# RoomIndicator_Outside.net
KiCad netlist of a schematic drawn in EAGLE
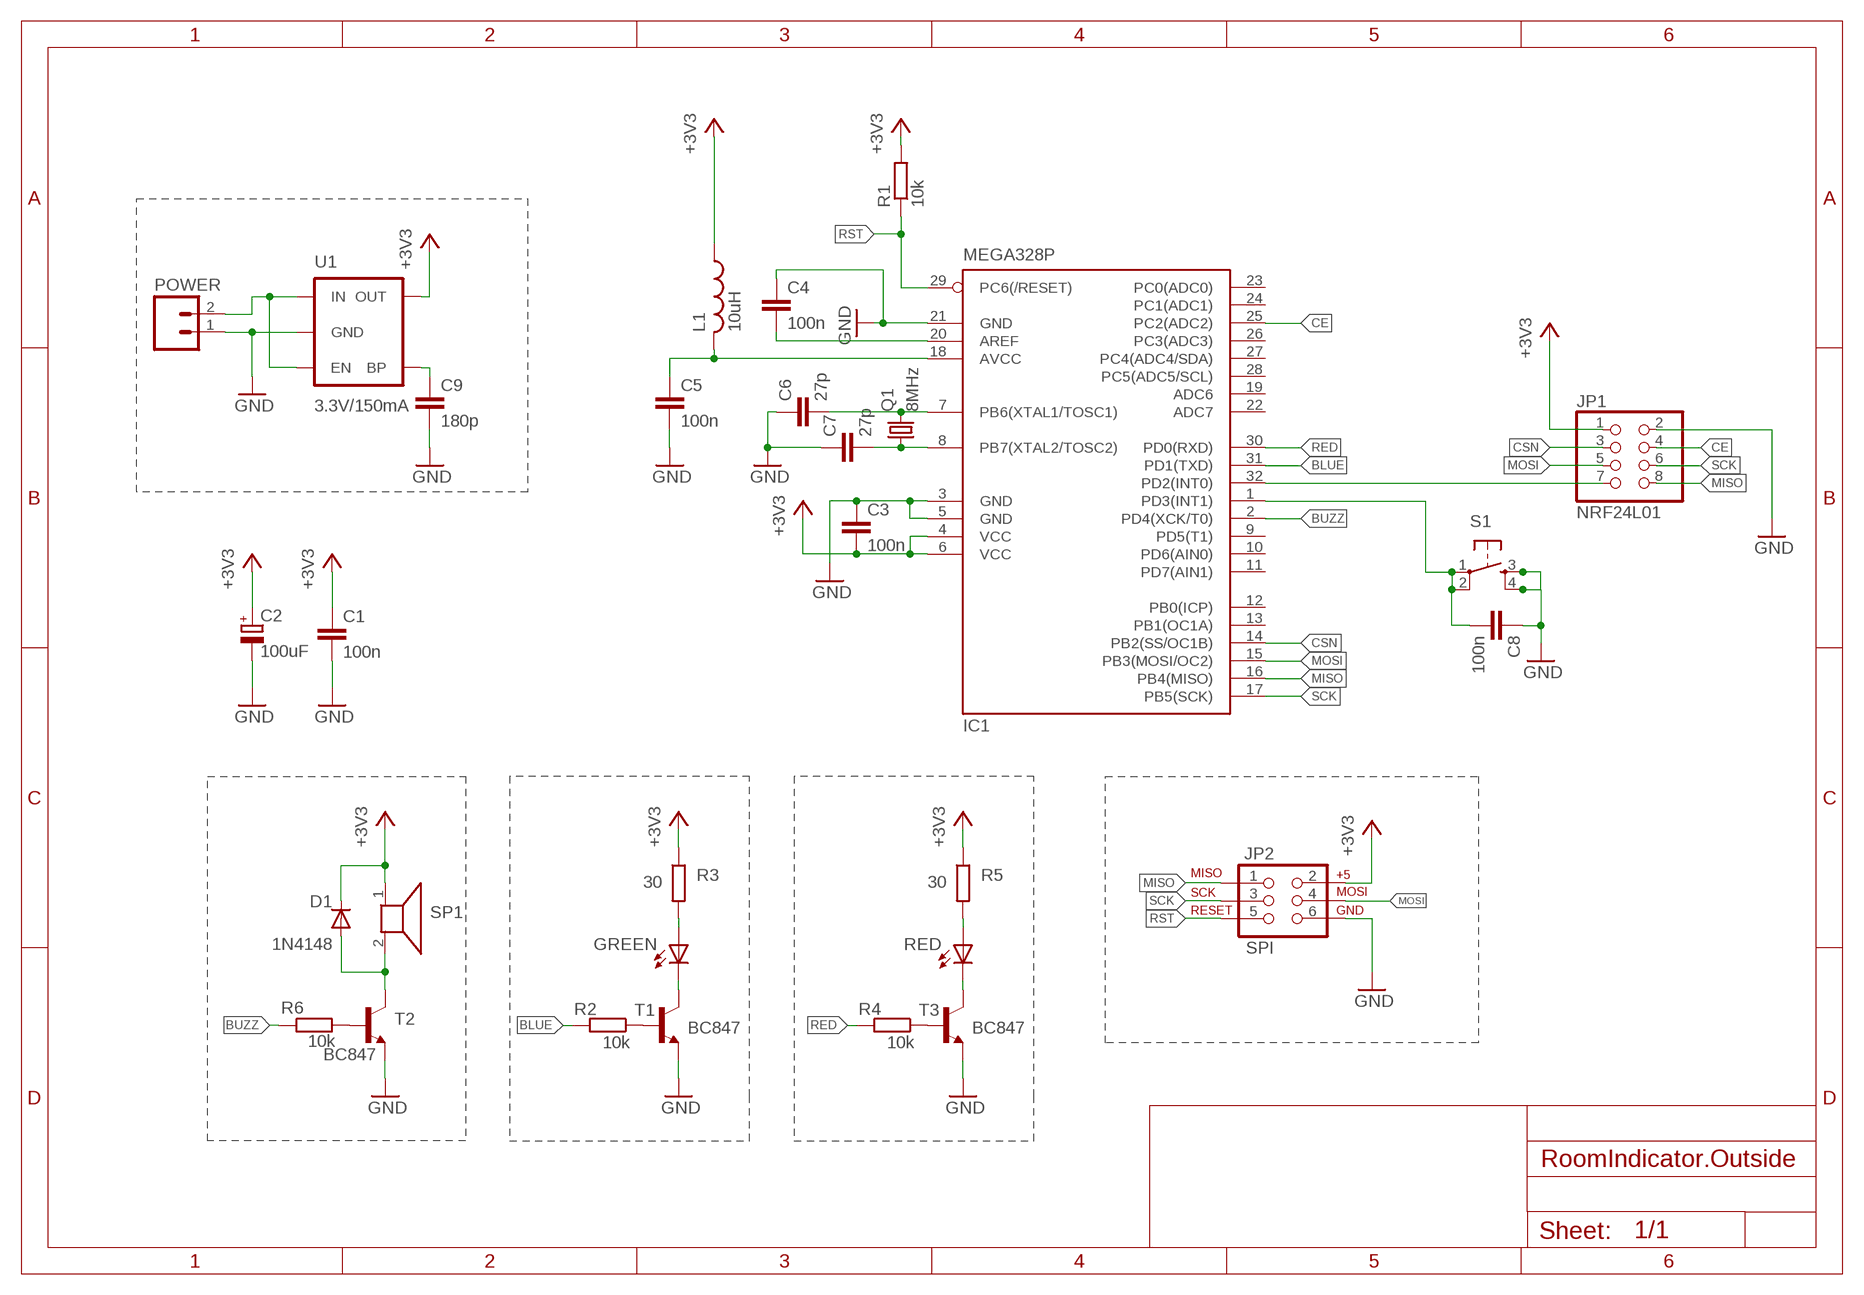
[diagram p0: schematic, sheet 1]

(export (version "E")
  (design (tool "Eeschema 10.0.6"))
  (components
    (comp (ref "C1")
      (value "100n")
      (footprint "eagle-import:C025-025X050")
      (libsource (lib "eagle-import") (part "C-EU025-025X050"))
    )
    (comp (ref "C2")
      (value "100uF")
      (footprint "eagle-import:E2,5-5")
      (libsource (lib "eagle-import") (part "CPOL-EUE2.5-5"))
    )
    (comp (ref "C3")
      (value "100n")
      (footprint "eagle-import:C0805K")
      (libsource (lib "eagle-import") (part "C-EUC0805K"))
    )
    (comp (ref "C4")
      (value "100n")
      (footprint "eagle-import:C0805K")
      (libsource (lib "eagle-import") (part "C-EUC0805K"))
    )
    (comp (ref "C5")
      (value "100n")
      (footprint "eagle-import:C0805K")
      (libsource (lib "eagle-import") (part "C-EUC0805K"))
    )
    (comp (ref "C6")
      (value "27p")
      (footprint "eagle-import:C0805K")
      (libsource (lib "eagle-import") (part "C-EUC0805K"))
    )
    (comp (ref "C7")
      (value "27p")
      (footprint "eagle-import:C0805K")
      (libsource (lib "eagle-import") (part "C-EUC0805K"))
    )
    (comp (ref "C8")
      (value "100n")
      (footprint "eagle-import:C0805K")
      (libsource (lib "eagle-import") (part "C-EUC0805K"))
    )
    (comp (ref "C9")
      (value "180p")
      (footprint "eagle-import:C0805K")
      (libsource (lib "eagle-import") (part "C-EUC0805K"))
    )
    (comp (ref "D1")
      (value "1N4148")
      (footprint "eagle-import:DO35-7")
      (libsource (lib "eagle-import") (part "1N4148DO35-7"))
    )
    (comp (ref "GREEN")
      (value "GREEN")
      (footprint "eagle-import:LED5MM")
      (libsource (lib "eagle-import") (part "LED5MM"))
    )
    (comp (ref "IC1")
      (value "MEGA328P")
      (footprint "eagle-import:TQFP32-08")
      (fields (field (name "MPN") "ATMEGA8-16AU"))
      (libsource (lib "eagle-import") (part "MEGA8-AI"))
    )
    (comp (ref "JP1")
      (value "NRF24L01")
      (footprint "eagle-import:2X04")
      (libsource (lib "eagle-import") (part "PINHD-2X4"))
    )
    (comp (ref "JP2")
      (value "SPI")
      (footprint "eagle-import:2X3")
      (libsource (lib "eagle-import") (part "AVR_SPI_PRG_6PTH"))
    )
    (comp (ref "L1")
      (value "10uH")
      (footprint "eagle-import:0204_7")
      (libsource (lib "eagle-import") (part "L-US0204/7"))
    )
    (comp (ref "POWER")
      (value "M02PTH")
      (footprint "eagle-import:1X02")
      (libsource (lib "eagle-import") (part "M02PTH"))
    )
    (comp (ref "Q1")
      (value "8MHz")
      (footprint "eagle-import:HC49_S")
      (libsource (lib "eagle-import") (part "CRYSTALHC49S"))
    )
    (comp (ref "R1")
      (value "10k")
      (footprint "eagle-import:R0805")
      (libsource (lib "eagle-import") (part "R-EU_R0805"))
    )
    (comp (ref "R2")
      (value "10k")
      (footprint "eagle-import:R0805")
      (libsource (lib "eagle-import") (part "R-EU_R0805"))
    )
    (comp (ref "R3")
      (value "30")
      (footprint "eagle-import:0204_5")
      (libsource (lib "eagle-import") (part "R-EU_0204/5"))
    )
    (comp (ref "R4")
      (value "10k")
      (footprint "eagle-import:R0805")
      (libsource (lib "eagle-import") (part "R-EU_R0805"))
    )
    (comp (ref "R5")
      (value "30")
      (footprint "eagle-import:0204_5")
      (libsource (lib "eagle-import") (part "R-EU_0204/5"))
    )
    (comp (ref "R6")
      (value "10k")
      (footprint "eagle-import:R0805")
      (libsource (lib "eagle-import") (part "R-EU_R0805"))
    )
    (comp (ref "RED")
      (value "GREEN")
      (footprint "eagle-import:LED5MM")
      (libsource (lib "eagle-import") (part "LED5MM"))
    )
    (comp (ref "S1")
      (value "TAC_SWITCHPTH")
      (footprint "eagle-import:TACTILE-PTH")
      (libsource (lib "eagle-import") (part "TAC_SWITCHPTH"))
    )
    (comp (ref "SP1")
      (value "AL60P")
      (footprint "eagle-import:AL60P")
      (libsource (lib "eagle-import") (part "AL60P"))
    )
    (comp (ref "T1")
      (value "BC847")
      (footprint "eagle-import:SOT23")
      (libsource (lib "eagle-import") (part "BC847"))
    )
    (comp (ref "T2")
      (value "BC847")
      (footprint "eagle-import:SOT23")
      (libsource (lib "eagle-import") (part "BC847"))
    )
    (comp (ref "T3")
      (value "BC847")
      (footprint "eagle-import:SOT23")
      (libsource (lib "eagle-import") (part "BC847"))
    )
    (comp (ref "U1")
      (value "3.3V/150mA")
      (footprint "eagle-import:SOT23-5")
      (libsource (lib "eagle-import") (part "V_REG_MIC52053.3V"))
    )
  )
  (nets
    (net (code "1") (name "+3V3") (class "Default")
      (node (ref "C1") (pin "1") (pinfunction "1_1") (pintype "passive"))
      (node (ref "C2") (pin "+") (pinfunction "+_+") (pintype "passive"))
      (node (ref "C3") (pin "2") (pinfunction "2_2") (pintype "passive"))
      (node (ref "D1") (pin "C") (pinfunction "C_C") (pintype "passive"))
      (node (ref "IC1") (pin "4") (pinfunction "VCC_4") (pintype "power_in"))
      (node (ref "IC1") (pin "6") (pinfunction "VCC_6") (pintype "power_in"))
      (node (ref "JP1") (pin "1") (pinfunction "1_1") (pintype "passive"))
      (node (ref "JP2") (pin "2") (pinfunction "2_2") (pintype "passive"))
      (node (ref "L1") (pin "1") (pinfunction "1_1") (pintype "passive"))
      (node (ref "R1") (pin "2") (pinfunction "2_2") (pintype "passive"))
      (node (ref "R3") (pin "1") (pinfunction "1_1") (pintype "passive"))
      (node (ref "R5") (pin "1") (pinfunction "1_1") (pintype "passive"))
      (node (ref "SP1") (pin "1") (pinfunction "1_1") (pintype "passive"))
      (node (ref "U1") (pin "5") (pinfunction "OUT_5") (pintype "passive"))
    )
    (net (code "2") (name "BLUE") (class "Default")
      (node (ref "IC1") (pin "31") (pinfunction "PD1(TXD)_31") (pintype "bidirectional"))
      (node (ref "R2") (pin "2") (pinfunction "2_2") (pintype "passive"))
    )
    (net (code "3") (name "BUZZ") (class "Default")
      (node (ref "IC1") (pin "2") (pinfunction "PD4(XCK/T0)_2") (pintype "bidirectional"))
      (node (ref "R6") (pin "1") (pinfunction "1_1") (pintype "passive"))
    )
    (net (code "4") (name "CE") (class "Default")
      (node (ref "IC1") (pin "25") (pinfunction "PC2(ADC2)_25") (pintype "bidirectional"))
      (node (ref "JP1") (pin "4") (pinfunction "4_4") (pintype "passive"))
    )
    (net (code "5") (name "CSN") (class "Default")
      (node (ref "IC1") (pin "14") (pinfunction "PB2(SS/OC1B)_14") (pintype "bidirectional"))
      (node (ref "JP1") (pin "3") (pinfunction "3_3") (pintype "passive"))
    )
    (net (code "6") (name "GND") (class "Default")
      (node (ref "C1") (pin "2") (pinfunction "2_2") (pintype "passive"))
      (node (ref "C2") (pin "-") (pinfunction "-_-") (pintype "passive"))
      (node (ref "C3") (pin "1") (pinfunction "1_1") (pintype "passive"))
      (node (ref "C4") (pin "1") (pinfunction "1_1") (pintype "passive"))
      (node (ref "C5") (pin "2") (pinfunction "2_2") (pintype "passive"))
      (node (ref "C6") (pin "1") (pinfunction "1_1") (pintype "passive"))
      (node (ref "C7") (pin "1") (pinfunction "1_1") (pintype "passive"))
      (node (ref "C8") (pin "1") (pinfunction "1_1") (pintype "passive"))
      (node (ref "C9") (pin "2") (pinfunction "2_2") (pintype "passive"))
      (node (ref "IC1") (pin "21") (pinfunction "GND_21") (pintype "power_in"))
      (node (ref "IC1") (pin "3") (pinfunction "GND_3") (pintype "power_in"))
      (node (ref "IC1") (pin "5") (pinfunction "GND_5") (pintype "power_in"))
      (node (ref "JP1") (pin "2") (pinfunction "2_2") (pintype "passive"))
      (node (ref "JP2") (pin "6") (pinfunction "6_6") (pintype "passive"))
      (node (ref "POWER") (pin "1") (pinfunction "1_1") (pintype "passive"))
      (node (ref "S1") (pin "3") (pinfunction "3_3") (pintype "passive"))
      (node (ref "S1") (pin "4") (pinfunction "4_4") (pintype "passive"))
      (node (ref "T1") (pin "2") (pinfunction "E_2") (pintype "passive"))
      (node (ref "T2") (pin "2") (pinfunction "E_2") (pintype "passive"))
      (node (ref "T3") (pin "2") (pinfunction "E_2") (pintype "passive"))
      (node (ref "U1") (pin "2") (pinfunction "GND_2") (pintype "input"))
    )
    (net (code "7") (name "MISO") (class "Default")
      (node (ref "IC1") (pin "16") (pinfunction "PB4(MISO)_16") (pintype "bidirectional"))
      (node (ref "JP1") (pin "8") (pinfunction "8_8") (pintype "passive"))
      (node (ref "JP2") (pin "1") (pinfunction "1_1") (pintype "passive"))
    )
    (net (code "8") (name "MOSI") (class "Default")
      (node (ref "IC1") (pin "15") (pinfunction "PB3(MOSI/OC2)_15") (pintype "bidirectional"))
      (node (ref "JP1") (pin "5") (pinfunction "5_5") (pintype "passive"))
      (node (ref "JP2") (pin "4") (pinfunction "4_4") (pintype "passive"))
    )
    (net (code "9") (name "Net-(GREEN-C)") (class "Default")
      (node (ref "GREEN") (pin "K") (pinfunction "C_K") (pintype "passive"))
      (node (ref "T1") (pin "3") (pinfunction "C_3") (pintype "passive"))
    )
    (net (code "10") (name "Net-(GREEN-PadA)") (class "Default")
      (node (ref "GREEN") (pin "A") (pinfunction "A_A") (pintype "passive"))
      (node (ref "R3") (pin "2") (pinfunction "2_2") (pintype "passive"))
    )
    (net (code "11") (name "Net-(IC1-AREF)") (class "Default")
      (node (ref "C4") (pin "2") (pinfunction "2_2") (pintype "passive"))
      (node (ref "IC1") (pin "20") (pinfunction "AREF_20") (pintype "passive"))
    )
    (net (code "12") (name "Net-(IC1-AVCC)") (class "Default")
      (node (ref "C5") (pin "1") (pinfunction "1_1") (pintype "passive"))
      (node (ref "IC1") (pin "18") (pinfunction "AVCC_18") (pintype "power_in"))
      (node (ref "L1") (pin "2") (pinfunction "2_2") (pintype "passive"))
    )
    (net (code "13") (name "Net-(IC1-PB6(XTAL1{slash}TOSC1))") (class "Default")
      (node (ref "C6") (pin "2") (pinfunction "2_2") (pintype "passive"))
      (node (ref "IC1") (pin "7") (pinfunction "PB6(XTAL1/TOSC1)_7") (pintype "bidirectional"))
      (node (ref "Q1") (pin "2") (pinfunction "2_2") (pintype "passive"))
    )
    (net (code "14") (name "Net-(IC1-PB7(XTAL2{slash}TOSC2))") (class "Default")
      (node (ref "C7") (pin "2") (pinfunction "2_2") (pintype "passive"))
      (node (ref "IC1") (pin "8") (pinfunction "PB7(XTAL2/TOSC2)_8") (pintype "bidirectional"))
      (node (ref "Q1") (pin "1") (pinfunction "1_1") (pintype "passive"))
    )
    (net (code "15") (name "Net-(IC1-PD2(INT0))") (class "Default")
      (node (ref "IC1") (pin "32") (pinfunction "PD2(INT0)_32") (pintype "bidirectional"))
      (node (ref "JP1") (pin "7") (pinfunction "7_7") (pintype "passive"))
    )
    (net (code "16") (name "Net-(IC1-PD3(INT1))") (class "Default")
      (node (ref "C8") (pin "2") (pinfunction "2_2") (pintype "passive"))
      (node (ref "IC1") (pin "1") (pinfunction "PD3(INT1)_1") (pintype "bidirectional"))
      (node (ref "S1") (pin "1") (pinfunction "1_1") (pintype "passive"))
      (node (ref "S1") (pin "2") (pinfunction "2_2") (pintype "passive"))
    )
    (net (code "17") (name "Net-(R5-Pad2)") (class "Default")
      (node (ref "R5") (pin "2") (pinfunction "2_2") (pintype "passive"))
      (node (ref "RED") (pin "A") (pinfunction "A_A") (pintype "passive"))
    )
    (net (code "18") (name "Net-(RED-C)") (class "Default")
      (node (ref "RED") (pin "K") (pinfunction "C_K") (pintype "passive"))
      (node (ref "T3") (pin "3") (pinfunction "C_3") (pintype "passive"))
    )
    (net (code "19") (name "Net-(T1-B)") (class "Default")
      (node (ref "R2") (pin "1") (pinfunction "1_1") (pintype "passive"))
      (node (ref "T1") (pin "1") (pinfunction "B_1") (pintype "passive"))
    )
    (net (code "20") (name "Net-(T2-B)") (class "Default")
      (node (ref "R6") (pin "2") (pinfunction "2_2") (pintype "passive"))
      (node (ref "T2") (pin "1") (pinfunction "B_1") (pintype "passive"))
    )
    (net (code "21") (name "Net-(T2-C)") (class "Default")
      (node (ref "D1") (pin "A") (pinfunction "A_A") (pintype "passive"))
      (node (ref "SP1") (pin "2") (pinfunction "2_2") (pintype "passive"))
      (node (ref "T2") (pin "3") (pinfunction "C_3") (pintype "passive"))
    )
    (net (code "22") (name "Net-(T3-B)") (class "Default")
      (node (ref "R4") (pin "1") (pinfunction "1_1") (pintype "passive"))
      (node (ref "T3") (pin "1") (pinfunction "B_1") (pintype "passive"))
    )
    (net (code "23") (name "Net-(U1-BP)") (class "Default")
      (node (ref "C9") (pin "1") (pinfunction "1_1") (pintype "passive"))
      (node (ref "U1") (pin "4") (pinfunction "BP_4") (pintype "input"))
    )
    (net (code "24") (name "Net-(U1-EN)") (class "Default")
      (node (ref "POWER") (pin "2") (pinfunction "2_2") (pintype "passive"))
      (node (ref "U1") (pin "1") (pinfunction "IN_1") (pintype "input"))
      (node (ref "U1") (pin "3") (pinfunction "EN_3") (pintype "input"))
    )
    (net (code "25") (name "RED") (class "Default")
      (node (ref "IC1") (pin "30") (pinfunction "PD0(RXD)_30") (pintype "bidirectional"))
      (node (ref "R4") (pin "2") (pinfunction "2_2") (pintype "passive"))
    )
    (net (code "26") (name "RST") (class "Default")
      (node (ref "IC1") (pin "29") (pinfunction "PC6(/RESET)_29") (pintype "bidirectional"))
      (node (ref "JP2") (pin "5") (pinfunction "5_5") (pintype "passive"))
      (node (ref "R1") (pin "1") (pinfunction "1_1") (pintype "passive"))
    )
    (net (code "27") (name "SCK") (class "Default")
      (node (ref "IC1") (pin "17") (pinfunction "PB5(SCK)_17") (pintype "bidirectional"))
      (node (ref "JP1") (pin "6") (pinfunction "6_6") (pintype "passive"))
      (node (ref "JP2") (pin "3") (pinfunction "3_3") (pintype "passive"))
    )
    (net (code "28") (name "unconnected-(IC1-ADC6-Pad19)") (class "Default")
      (node (ref "IC1") (pin "19") (pinfunction "ADC6_19") (pintype "bidirectional"))
    )
    (net (code "29") (name "unconnected-(IC1-ADC7-Pad22)") (class "Default")
      (node (ref "IC1") (pin "22") (pinfunction "ADC7_22") (pintype "bidirectional"))
    )
    (net (code "30") (name "unconnected-(IC1-PB0(ICP)-Pad12)") (class "Default")
      (node (ref "IC1") (pin "12") (pinfunction "PB0(ICP)_12") (pintype "bidirectional"))
    )
    (net (code "31") (name "unconnected-(IC1-PB1(OC1A)-Pad13)") (class "Default")
      (node (ref "IC1") (pin "13") (pinfunction "PB1(OC1A)_13") (pintype "bidirectional"))
    )
    (net (code "32") (name "unconnected-(IC1-PC0(ADC0)-Pad23)") (class "Default")
      (node (ref "IC1") (pin "23") (pinfunction "PC0(ADC0)_23") (pintype "bidirectional"))
    )
    (net (code "33") (name "unconnected-(IC1-PC1(ADC1)-Pad24)") (class "Default")
      (node (ref "IC1") (pin "24") (pinfunction "PC1(ADC1)_24") (pintype "bidirectional"))
    )
    (net (code "34") (name "unconnected-(IC1-PC3(ADC3)-Pad26)") (class "Default")
      (node (ref "IC1") (pin "26") (pinfunction "PC3(ADC3)_26") (pintype "bidirectional"))
    )
    (net (code "35") (name "unconnected-(IC1-PC4(ADC4{slash}SDA)-Pad27)") (class "Default")
      (node (ref "IC1") (pin "27") (pinfunction "PC4(ADC4/SDA)_27") (pintype "bidirectional"))
    )
    (net (code "36") (name "unconnected-(IC1-PC5(ADC5{slash}SCL)-Pad28)") (class "Default")
      (node (ref "IC1") (pin "28") (pinfunction "PC5(ADC5/SCL)_28") (pintype "bidirectional"))
    )
    (net (code "37") (name "unconnected-(IC1-PD5(T1)-Pad9)") (class "Default")
      (node (ref "IC1") (pin "9") (pinfunction "PD5(T1)_9") (pintype "bidirectional"))
    )
    (net (code "38") (name "unconnected-(IC1-PD6(AIN0)-Pad10)") (class "Default")
      (node (ref "IC1") (pin "10") (pinfunction "PD6(AIN0)_10") (pintype "bidirectional"))
    )
    (net (code "39") (name "unconnected-(IC1-PD7(AIN1)-Pad11)") (class "Default")
      (node (ref "IC1") (pin "11") (pinfunction "PD7(AIN1)_11") (pintype "bidirectional"))
    )
  )
)
